# Sheet1.net
KiCad netlist of a schematic drawn in Altium Designer
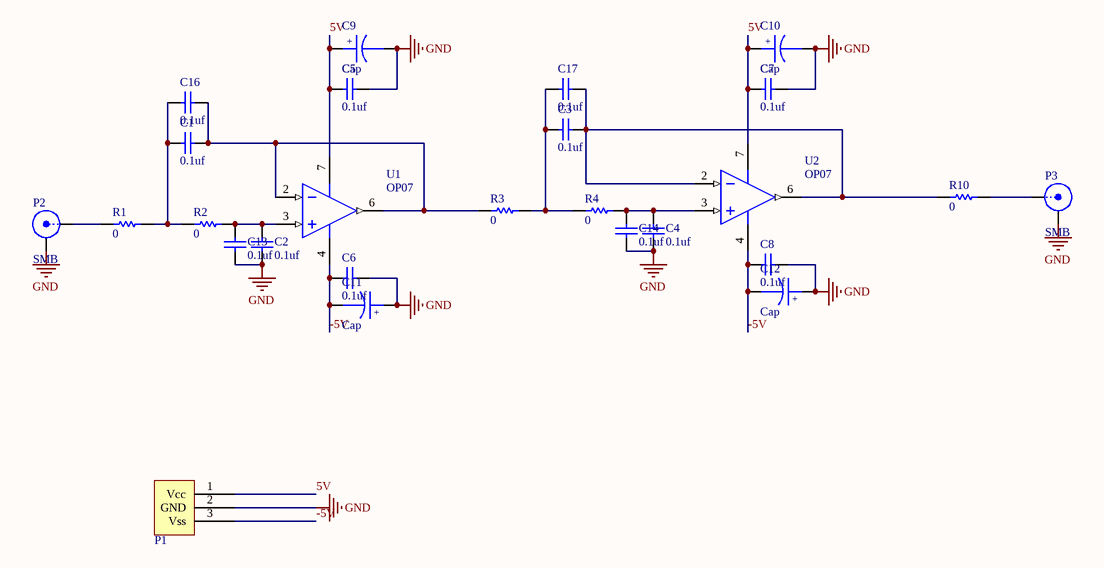
[diagram p0: Sheet1.SchDoc]

(export (version "E")
  (design (tool "Eeschema 10.0.6"))
  (components
    (comp (ref "C1") (value "0.1uf") (footprint "0805") (libsource (lib "Schlib1") (part "Cap")))
    (comp (ref "C2") (value "0.1uf") (footprint "0805") (libsource (lib "Schlib1") (part "Cap")))
    (comp (ref "C3") (value "0.1uf") (footprint "0805") (libsource (lib "Schlib1") (part "Cap")))
    (comp (ref "C4") (value "0.1uf") (footprint "0805") (libsource (lib "Schlib1") (part "Cap")))
    (comp (ref "C5") (value "0.1uf") (footprint "0805") (libsource (lib "Schlib1") (part "Cap")))
    (comp (ref "C6") (value "0.1uf") (footprint "0805") (libsource (lib "Schlib1") (part "Cap")))
    (comp (ref "C7") (value "0.1uf") (footprint "0805") (libsource (lib "Schlib1") (part "Cap")))
    (comp (ref "C8") (value "0.1uf") (footprint "0805") (libsource (lib "Schlib1") (part "Cap")))
    (comp (ref "C9")
      (value "Cap")
      (footprint "3216C-TYPE_A")
      (libsource (lib "Schlib1") (part "Tantalium Cap"))
    )
    (comp (ref "C10")
      (value "Cap")
      (footprint "3216C-TYPE_A")
      (libsource (lib "Schlib1") (part "Tantalium Cap"))
    )
    (comp (ref "C11")
      (value "Cap")
      (footprint "3216C-TYPE_A")
      (libsource (lib "Schlib1") (part "Tantalium Cap"))
    )
    (comp (ref "C12")
      (value "Cap")
      (footprint "3216C-TYPE_A")
      (libsource (lib "Schlib1") (part "Tantalium Cap"))
    )
    (comp (ref "C13") (value "0.1uf") (footprint "0805") (libsource (lib "Schlib1") (part "Cap")))
    (comp (ref "C14") (value "0.1uf") (footprint "0805") (libsource (lib "Schlib1") (part "Cap")))
    (comp (ref "C16") (value "0.1uf") (footprint "0805") (libsource (lib "Schlib1") (part "Cap")))
    (comp (ref "C17") (value "0.1uf") (footprint "0805") (libsource (lib "Schlib1") (part "Cap")))
    (comp (ref "P1")
      (value "XH2.54-3p")
      (footprint "XH2.54-3p")
      (libsource (lib "Schlib1") (part "XH2.54-3p"))
    )
    (comp (ref "P2")
      (value "SMB")
      (footprint "SMB_V-RJ45")
      (description "SMB Straight Connector")
      (fields (field (name "PUBLISHER") "Altium Limited"))
      (libsource (lib "Miscellaneous Connectors") (part "SMB"))
    )
    (comp (ref "P3")
      (value "SMB")
      (footprint "SMB_V-RJ45")
      (description "SMB Straight Connector")
      (fields (field (name "PUBLISHER") "Altium Limited"))
      (libsource (lib "Miscellaneous Connectors") (part "SMB"))
    )
    (comp (ref "R1") (value "0") (footprint "0805") (libsource (lib "Schlib1") (part "Res")))
    (comp (ref "R2") (value "0") (footprint "0805") (libsource (lib "Schlib1") (part "Res")))
    (comp (ref "R3") (value "0") (footprint "0805") (libsource (lib "Schlib1") (part "Res")))
    (comp (ref "R4") (value "0") (footprint "0805") (libsource (lib "Schlib1") (part "Res")))
    (comp (ref "R10") (value "0") (footprint "0805") (libsource (lib "Schlib1") (part "Res")))
    (comp (ref "U1") (value "OP07") (footprint "TI-JG8") (libsource (lib "Schlib1") (part "OP07")))
    (comp (ref "U2") (value "OP07") (footprint "TI-JG8") (libsource (lib "Schlib1") (part "OP07")))
  )
  (nets
    (net (code "1") (name "/-5V") (class "Default")
      (node (ref "C11") (pin "2") (pinfunction "2_2") (pintype "passive"))
      (node (ref "C12") (pin "2") (pinfunction "2_2") (pintype "passive"))
      (node (ref "C6") (pin "1") (pinfunction "1_1") (pintype "passive"))
      (node (ref "C8") (pin "1") (pinfunction "1_1") (pintype "passive"))
      (node (ref "P1") (pin "3") (pinfunction "Vss_3") (pintype "passive"))
      (node (ref "U1") (pin "4") (pinfunction "V-_4") (pintype "power_in"))
      (node (ref "U2") (pin "4") (pinfunction "V-_4") (pintype "power_in"))
    )
    (net (code "2") (name "/5V") (class "Default")
      (node (ref "C10") (pin "1") (pinfunction "1_1") (pintype "passive"))
      (node (ref "C5") (pin "1") (pinfunction "1_1") (pintype "passive"))
      (node (ref "C7") (pin "1") (pinfunction "1_1") (pintype "passive"))
      (node (ref "C9") (pin "1") (pinfunction "1_1") (pintype "passive"))
      (node (ref "P1") (pin "1") (pinfunction "Vcc_1") (pintype "passive"))
      (node (ref "U1") (pin "7") (pinfunction "V+_7") (pintype "power_in"))
      (node (ref "U2") (pin "7") (pinfunction "V+_7") (pintype "power_in"))
    )
    (net (code "3") (name "GND") (class "Default")
      (node (ref "C10") (pin "2") (pinfunction "2_2") (pintype "passive"))
      (node (ref "C11") (pin "1") (pinfunction "1_1") (pintype "passive"))
      (node (ref "C12") (pin "1") (pinfunction "1_1") (pintype "passive"))
      (node (ref "C13") (pin "1") (pinfunction "1_1") (pintype "passive"))
      (node (ref "C14") (pin "1") (pinfunction "1_1") (pintype "passive"))
      (node (ref "C2") (pin "2") (pinfunction "2_2") (pintype "passive"))
      (node (ref "C4") (pin "1") (pinfunction "1_1") (pintype "passive"))
      (node (ref "C5") (pin "2") (pinfunction "2_2") (pintype "passive"))
      (node (ref "C6") (pin "2") (pinfunction "2_2") (pintype "passive"))
      (node (ref "C7") (pin "2") (pinfunction "2_2") (pintype "passive"))
      (node (ref "C8") (pin "2") (pinfunction "2_2") (pintype "passive"))
      (node (ref "C9") (pin "2") (pinfunction "2_2") (pintype "passive"))
      (node (ref "P1") (pin "2") (pinfunction "GND_2") (pintype "passive"))
      (node (ref "P2") (pin "2") (pinfunction "Y_2") (pintype "passive"))
      (node (ref "P3") (pin "2") (pinfunction "Y_2") (pintype "passive"))
    )
    (net (code "4") (name "Net-(C1-Pad2)") (class "Default")
      (node (ref "C1") (pin "2") (pinfunction "2_2") (pintype "passive"))
      (node (ref "C16") (pin "2") (pinfunction "2_2") (pintype "passive"))
      (node (ref "R1") (pin "2") (pinfunction "2_2") (pintype "passive"))
      (node (ref "R2") (pin "1") (pinfunction "1_1") (pintype "passive"))
    )
    (net (code "5") (name "Net-(C17-Pad2)") (class "Default")
      (node (ref "C17") (pin "2") (pinfunction "2_2") (pintype "passive"))
      (node (ref "C3") (pin "1") (pinfunction "1_1") (pintype "passive"))
      (node (ref "R3") (pin "2") (pinfunction "2_2") (pintype "passive"))
      (node (ref "R4") (pin "1") (pinfunction "1_1") (pintype "passive"))
    )
    (net (code "6") (name "Net-(P2-X)") (class "Default")
      (node (ref "P2") (pin "1") (pinfunction "X_1") (pintype "passive"))
      (node (ref "R1") (pin "1") (pinfunction "1_1") (pintype "passive"))
    )
    (net (code "7") (name "Net-(P3-X)") (class "Default")
      (node (ref "P3") (pin "1") (pinfunction "X_1") (pintype "passive"))
      (node (ref "R10") (pin "2") (pinfunction "2_2") (pintype "passive"))
    )
    (net (code "8") (name "Net-(U1-IN+)") (class "Default")
      (node (ref "C13") (pin "2") (pinfunction "2_2") (pintype "passive"))
      (node (ref "C2") (pin "1") (pinfunction "1_1") (pintype "passive"))
      (node (ref "R2") (pin "2") (pinfunction "2_2") (pintype "passive"))
      (node (ref "U1") (pin "3") (pinfunction "IN+_3") (pintype "input"))
    )
    (net (code "9") (name "Net-(U1-IN-)") (class "Default")
      (node (ref "C1") (pin "1") (pinfunction "1_1") (pintype "passive"))
      (node (ref "C16") (pin "1") (pinfunction "1_1") (pintype "passive"))
      (node (ref "R3") (pin "1") (pinfunction "1_1") (pintype "passive"))
      (node (ref "U1") (pin "2") (pinfunction "IN-_2") (pintype "input"))
      (node (ref "U1") (pin "6") (pinfunction "OUT_6") (pintype "output"))
    )
    (net (code "10") (name "Net-(U2-IN+)") (class "Default")
      (node (ref "C14") (pin "2") (pinfunction "2_2") (pintype "passive"))
      (node (ref "C4") (pin "2") (pinfunction "2_2") (pintype "passive"))
      (node (ref "R4") (pin "2") (pinfunction "2_2") (pintype "passive"))
      (node (ref "U2") (pin "3") (pinfunction "IN+_3") (pintype "input"))
    )
    (net (code "11") (name "Net-(U2-IN-)") (class "Default")
      (node (ref "C17") (pin "1") (pinfunction "1_1") (pintype "passive"))
      (node (ref "C3") (pin "2") (pinfunction "2_2") (pintype "passive"))
      (node (ref "R10") (pin "1") (pinfunction "1_1") (pintype "passive"))
      (node (ref "U2") (pin "2") (pinfunction "IN-_2") (pintype "input"))
      (node (ref "U2") (pin "6") (pinfunction "OUT_6") (pintype "output"))
    )
  )
)
